# linefollower.net
KiCad netlist of a schematic drawn in EAGLE
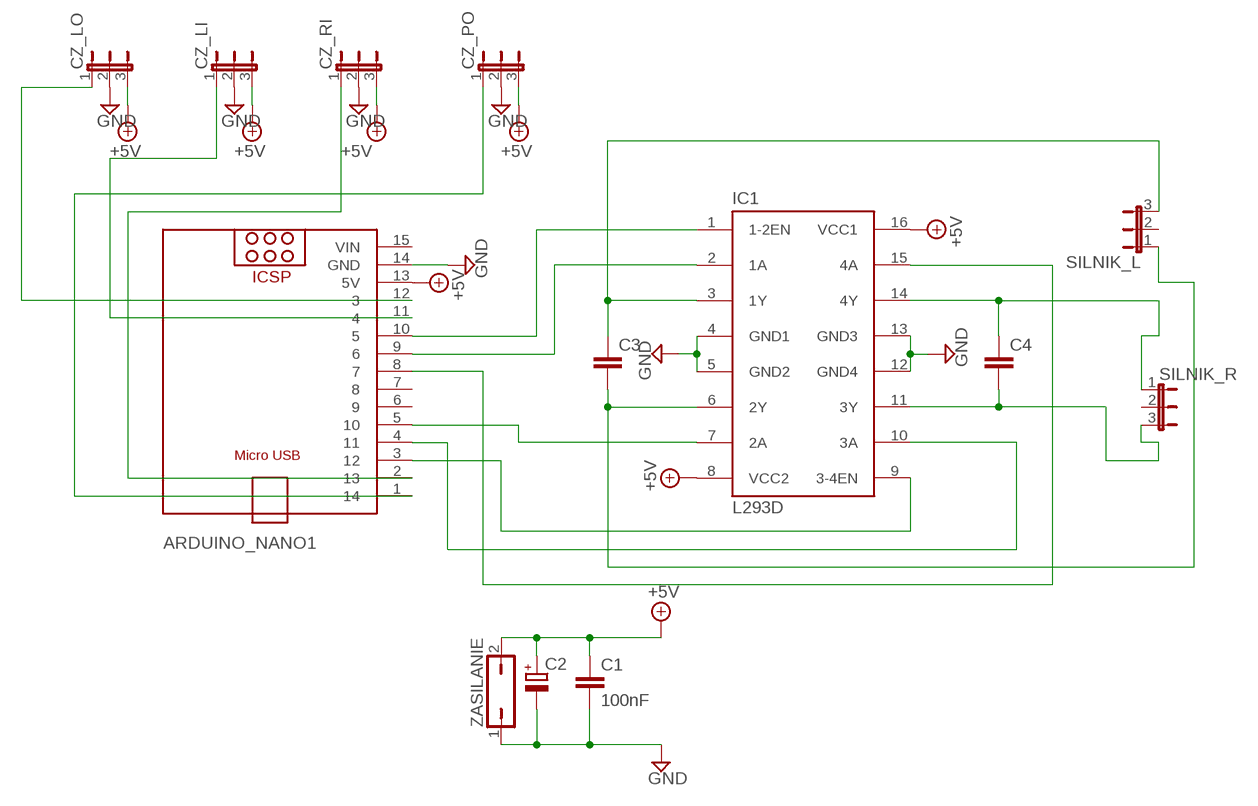
[diagram p0: schematic, sheet 1]

(export (version "E")
  (design (tool "Eeschema 10.0.6"))
  (components
    (comp (ref "ARDUINO_NANO1")
      (value "MH-TINY")
      (footprint "eagle-import:MH-TINY")
      (libsource (lib "eagle-import") (part "MH-TINY"))
    )
    (comp (ref "C1")
      (value "100nF")
      (footprint "eagle-import:C025-025X050")
      (libsource (lib "eagle-import") (part "C-EU025-025X050"))
    )
    (comp (ref "C2")
      (value "CPOL-EUE3.5-8")
      (footprint "eagle-import:E3,5-8")
      (libsource (lib "eagle-import") (part "CPOL-EUE3.5-8"))
    )
    (comp (ref "C3")
      (value "C-EU050-025X075")
      (footprint "eagle-import:C050-025X075")
      (libsource (lib "eagle-import") (part "C-EU050-025X075"))
    )
    (comp (ref "C4")
      (value "C-EU050-025X075")
      (footprint "eagle-import:C050-025X075")
      (libsource (lib "eagle-import") (part "C-EU050-025X075"))
    )
    (comp (ref "CZ_LI")
      (value "JP2E")
      (footprint "eagle-import:JP2")
      (libsource (lib "eagle-import") (part "JP2E"))
    )
    (comp (ref "CZ_LO")
      (value "JP2E")
      (footprint "eagle-import:JP2")
      (libsource (lib "eagle-import") (part "JP2E"))
    )
    (comp (ref "CZ_PO")
      (value "JP2E")
      (footprint "eagle-import:JP2")
      (libsource (lib "eagle-import") (part "JP2E"))
    )
    (comp (ref "CZ_RI")
      (value "JP2E")
      (footprint "eagle-import:JP2")
      (libsource (lib "eagle-import") (part "JP2E"))
    )
    (comp (ref "IC1")
      (value "L293D")
      (footprint "eagle-import:DIL16")
      (libsource (lib "eagle-import") (part "L293D"))
    )
    (comp (ref "SILNIK_L")
      (value "JP2E")
      (footprint "eagle-import:JP2")
      (libsource (lib "eagle-import") (part "JP2E"))
    )
    (comp (ref "SILNIK_R")
      (value "JP2E")
      (footprint "eagle-import:JP2")
      (libsource (lib "eagle-import") (part "JP2E"))
    )
    (comp (ref "ZASILANIE")
      (value "JP1Q")
      (footprint "eagle-import:JP1")
      (libsource (lib "eagle-import") (part "JP1Q"))
    )
  )
  (nets
    (net (code "1") (name "+5V") (class "Default")
      (node (ref "ARDUINO_NANO1") (pin "13") (pinfunction "5V_13") (pintype "power_in"))
      (node (ref "C1") (pin "1") (pinfunction "1_1") (pintype "passive"))
      (node (ref "C2") (pin "+") (pinfunction "+_+") (pintype "passive"))
      (node (ref "CZ_LI") (pin "3") (pinfunction "3_3") (pintype "passive"))
      (node (ref "CZ_LO") (pin "3") (pinfunction "3_3") (pintype "passive"))
      (node (ref "CZ_PO") (pin "3") (pinfunction "3_3") (pintype "passive"))
      (node (ref "CZ_RI") (pin "3") (pinfunction "3_3") (pintype "passive"))
      (node (ref "IC1") (pin "16") (pinfunction "VCC1_16") (pintype "power_in"))
      (node (ref "IC1") (pin "8") (pinfunction "VCC2_8") (pintype "power_in"))
      (node (ref "ZASILANIE") (pin "2") (pinfunction "2_2") (pintype "passive"))
    )
    (net (code "2") (name "/VIN") (class "Default")
      (node (ref "ARDUINO_NANO1") (pin "15") (pinfunction "VIN_15") (pintype "power_in"))
    )
    (net (code "3") (name "GND") (class "Default")
      (node (ref "ARDUINO_NANO1") (pin "14") (pinfunction "GND_14") (pintype "power_in"))
      (node (ref "C1") (pin "2") (pinfunction "2_2") (pintype "passive"))
      (node (ref "C2") (pin "-") (pinfunction "-_-") (pintype "passive"))
      (node (ref "CZ_LI") (pin "2") (pinfunction "2_2") (pintype "passive"))
      (node (ref "CZ_LO") (pin "2") (pinfunction "2_2") (pintype "passive"))
      (node (ref "CZ_PO") (pin "2") (pinfunction "2_2") (pintype "passive"))
      (node (ref "CZ_RI") (pin "2") (pinfunction "2_2") (pintype "passive"))
      (node (ref "IC1") (pin "12") (pinfunction "GND4_12") (pintype "power_in"))
      (node (ref "IC1") (pin "13") (pinfunction "GND3_13") (pintype "power_in"))
      (node (ref "IC1") (pin "4") (pinfunction "GND1_4") (pintype "power_in"))
      (node (ref "IC1") (pin "5") (pinfunction "GND2_5") (pintype "power_in"))
      (node (ref "ZASILANIE") (pin "1") (pinfunction "1_1") (pintype "passive"))
    )
    (net (code "4") (name "Net-(ARDUINO_NANO1-3)") (class "Default")
      (node (ref "ARDUINO_NANO1") (pin "12") (pinfunction "3_12") (pintype "bidirectional"))
      (node (ref "CZ_LO") (pin "1") (pinfunction "1_1") (pintype "passive"))
    )
    (net (code "5") (name "Net-(ARDUINO_NANO1-4)") (class "Default")
      (node (ref "ARDUINO_NANO1") (pin "11") (pinfunction "4_11") (pintype "bidirectional"))
      (node (ref "CZ_LI") (pin "1") (pinfunction "1_1") (pintype "passive"))
    )
    (net (code "6") (name "Net-(ARDUINO_NANO1-5)") (class "Default")
      (node (ref "ARDUINO_NANO1") (pin "10") (pinfunction "5_10") (pintype "bidirectional"))
      (node (ref "IC1") (pin "1") (pinfunction "1-2EN_1") (pintype "input"))
    )
    (net (code "7") (name "Net-(ARDUINO_NANO1-6)") (class "Default")
      (node (ref "ARDUINO_NANO1") (pin "9") (pinfunction "6_9") (pintype "bidirectional"))
      (node (ref "IC1") (pin "2") (pinfunction "1A_2") (pintype "input"))
    )
    (net (code "8") (name "Net-(ARDUINO_NANO1-7)") (class "Default")
      (node (ref "ARDUINO_NANO1") (pin "8") (pinfunction "7_8") (pintype "bidirectional"))
      (node (ref "IC1") (pin "15") (pinfunction "4A_15") (pintype "input"))
    )
    (net (code "9") (name "Net-(ARDUINO_NANO1-10)") (class "Default")
      (node (ref "ARDUINO_NANO1") (pin "5") (pinfunction "10_5") (pintype "bidirectional"))
      (node (ref "IC1") (pin "7") (pinfunction "2A_7") (pintype "input"))
    )
    (net (code "10") (name "Net-(ARDUINO_NANO1-11)") (class "Default")
      (node (ref "ARDUINO_NANO1") (pin "4") (pinfunction "11_4") (pintype "bidirectional"))
      (node (ref "IC1") (pin "10") (pinfunction "3A_10") (pintype "input"))
    )
    (net (code "11") (name "Net-(ARDUINO_NANO1-12)") (class "Default")
      (node (ref "ARDUINO_NANO1") (pin "3") (pinfunction "12_3") (pintype "bidirectional"))
      (node (ref "IC1") (pin "9") (pinfunction "3-4EN_9") (pintype "input"))
    )
    (net (code "12") (name "Net-(ARDUINO_NANO1-13)") (class "Default")
      (node (ref "ARDUINO_NANO1") (pin "2") (pinfunction "13_2") (pintype "bidirectional"))
      (node (ref "CZ_RI") (pin "1") (pinfunction "1_1") (pintype "passive"))
    )
    (net (code "13") (name "Net-(ARDUINO_NANO1-14)") (class "Default")
      (node (ref "ARDUINO_NANO1") (pin "1") (pinfunction "14_1") (pintype "bidirectional"))
      (node (ref "CZ_PO") (pin "1") (pinfunction "1_1") (pintype "passive"))
    )
    (net (code "14") (name "Net-(IC1-1Y)") (class "Default")
      (node (ref "C3") (pin "1") (pinfunction "1_1") (pintype "passive"))
      (node (ref "IC1") (pin "3") (pinfunction "1Y_3") (pintype "output"))
      (node (ref "SILNIK_L") (pin "3") (pinfunction "3_3") (pintype "passive"))
    )
    (net (code "15") (name "Net-(IC1-2Y)") (class "Default")
      (node (ref "C3") (pin "2") (pinfunction "2_2") (pintype "passive"))
      (node (ref "IC1") (pin "6") (pinfunction "2Y_6") (pintype "output"))
      (node (ref "SILNIK_L") (pin "1") (pinfunction "1_1") (pintype "passive"))
    )
    (net (code "16") (name "Net-(IC1-3Y)") (class "Default")
      (node (ref "C4") (pin "2") (pinfunction "2_2") (pintype "passive"))
      (node (ref "IC1") (pin "11") (pinfunction "3Y_11") (pintype "output"))
      (node (ref "SILNIK_R") (pin "3") (pinfunction "3_3") (pintype "passive"))
    )
    (net (code "17") (name "Net-(IC1-4Y)") (class "Default")
      (node (ref "C4") (pin "1") (pinfunction "1_1") (pintype "passive"))
      (node (ref "IC1") (pin "14") (pinfunction "4Y_14") (pintype "output"))
      (node (ref "SILNIK_R") (pin "1") (pinfunction "1_1") (pintype "passive"))
    )
    (net (code "18") (name "unconnected-(ARDUINO_NANO1-8-Pad7)") (class "Default")
      (node (ref "ARDUINO_NANO1") (pin "7") (pinfunction "8_7") (pintype "bidirectional"))
    )
    (net (code "19") (name "unconnected-(ARDUINO_NANO1-9-Pad6)") (class "Default")
      (node (ref "ARDUINO_NANO1") (pin "6") (pinfunction "9_6") (pintype "bidirectional"))
    )
    (net (code "20") (name "unconnected-(SILNIK_L-Pad2)") (class "Default")
      (node (ref "SILNIK_L") (pin "2") (pinfunction "2_2") (pintype "passive"))
    )
    (net (code "21") (name "unconnected-(SILNIK_R-Pad2)") (class "Default")
      (node (ref "SILNIK_R") (pin "2") (pinfunction "2_2") (pintype "passive"))
    )
  )
)
